# OuterMaskFinal.net
KiCad netlist of a schematic drawn in Altium Designer
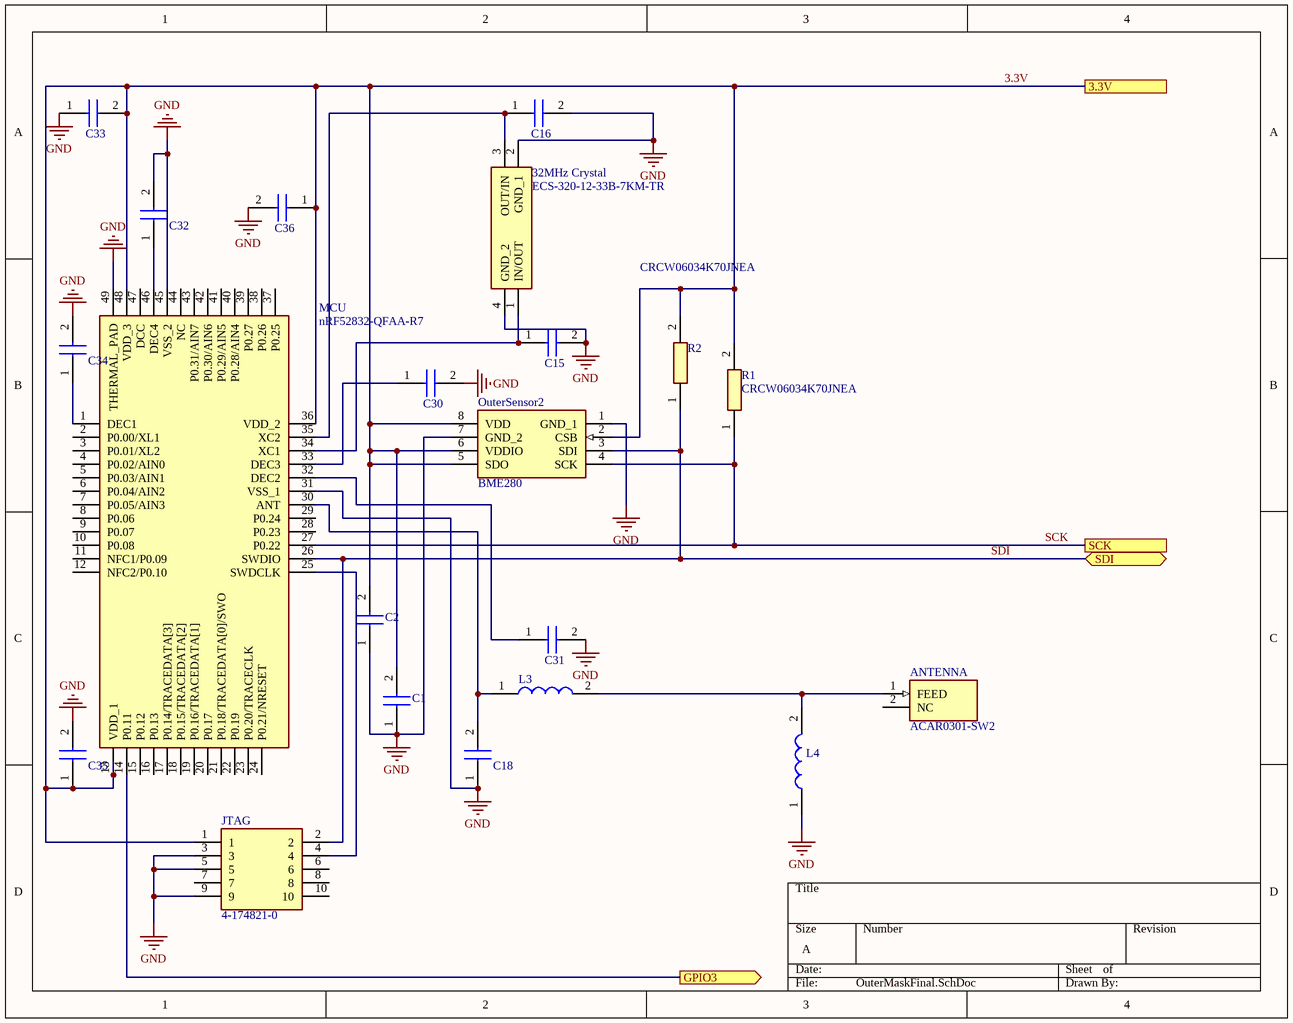
[diagram p0: OuterMaskFinal.SchDoc]

(export (version "E")
  (design (tool "Eeschema 10.0.6"))
  (components
    (comp (ref "32MHz Crystal")
      (value "ECS-320-12-33B-7KM-TR")
      (footprint "SamacSys:ECS3201233B7KMTR")
      (description "Crystal or Oscillator")
      (fields (field (name "MOUSER PART NUMBER") "520-320-12-33B-7KM-T"))
      (libsource (lib "*") (part "ECS-320-12-33B-7KM-TR"))
    )
    (comp (ref "ANTENNA")
      (value "ACAR0301-SW2")
      (footprint "SamacSys:ANTC3016X70N")
      (description "Antenna")
      (fields (field (name "MOUSER PART NUMBER") "815-ACAR0301-SW2"))
      (libsource (lib "*") (part "ACAR0301-SW2"))
    )
    (comp (ref "C1")
      (value "06033C334KAT2A")
      (footprint "SamacSys:CAPC1608X90N")
      (description "Capacitor")
      (fields (field (name "MOUSER PART NUMBER") "581-06033C334KAT2A"))
      (libsource (lib "*") (part "06033C334KAT2A"))
    )
    (comp (ref "C2")
      (value "06033C334KAT2A")
      (footprint "SamacSys:CAPC1608X90N")
      (description "Capacitor")
      (fields (field (name "MOUSER PART NUMBER") "581-06033C334KAT2A"))
      (libsource (lib "*") (part "06033C334KAT2A"))
    )
    (comp (ref "C15")
      (value "06033C334KAT2A")
      (footprint "SamacSys:CAPC1608X90N")
      (description "Capacitor")
      (fields (field (name "MOUSER PART NUMBER") "581-06033C334KAT2A"))
      (libsource (lib "*") (part "06033C334KAT2A"))
    )
    (comp (ref "C16")
      (value "06033C334KAT2A")
      (footprint "SamacSys:CAPC1608X90N")
      (description "Capacitor")
      (fields (field (name "MOUSER PART NUMBER") "581-06033C334KAT2A"))
      (libsource (lib "*") (part "06033C334KAT2A"))
    )
    (comp (ref "C18")
      (value "06033C334KAT2A")
      (footprint "SamacSys:CAPC1608X90N")
      (description "Capacitor")
      (fields (field (name "MOUSER PART NUMBER") "581-06033C334KAT2A"))
      (libsource (lib "*") (part "06033C334KAT2A"))
    )
    (comp (ref "C30")
      (value "06033C334KAT2A")
      (footprint "SamacSys:CAPC1608X90N")
      (description "Capacitor")
      (fields (field (name "MOUSER PART NUMBER") "581-06033C334KAT2A"))
      (libsource (lib "*") (part "06033C334KAT2A"))
    )
    (comp (ref "C31")
      (value "06033C334KAT2A")
      (footprint "SamacSys:CAPC1608X90N")
      (description "Capacitor")
      (fields (field (name "MOUSER PART NUMBER") "581-06033C334KAT2A"))
      (libsource (lib "*") (part "06033C334KAT2A"))
    )
    (comp (ref "C32")
      (value "06033C334KAT2A")
      (footprint "SamacSys:CAPC1608X90N")
      (description "Capacitor")
      (fields (field (name "MOUSER PART NUMBER") "581-06033C334KAT2A"))
      (libsource (lib "*") (part "06033C334KAT2A"))
    )
    (comp (ref "C33")
      (value "06033C334KAT2A")
      (footprint "SamacSys:CAPC1608X90N")
      (description "Capacitor")
      (fields (field (name "MOUSER PART NUMBER") "581-06033C334KAT2A"))
      (libsource (lib "*") (part "06033C334KAT2A"))
    )
    (comp (ref "C34")
      (value "06033C334KAT2A")
      (footprint "SamacSys:CAPC1608X90N")
      (description "Capacitor")
      (fields (field (name "MOUSER PART NUMBER") "581-06033C334KAT2A"))
      (libsource (lib "*") (part "06033C334KAT2A"))
    )
    (comp (ref "C35")
      (value "06033C334KAT2A")
      (footprint "SamacSys:CAPC1608X90N")
      (description "Capacitor")
      (fields (field (name "MOUSER PART NUMBER") "581-06033C334KAT2A"))
      (libsource (lib "*") (part "06033C334KAT2A"))
    )
    (comp (ref "C36")
      (value "06033C334KAT2A")
      (footprint "SamacSys:CAPC1608X90N")
      (description "Capacitor")
      (fields (field (name "MOUSER PART NUMBER") "581-06033C334KAT2A"))
      (libsource (lib "*") (part "06033C334KAT2A"))
    )
    (comp (ref "JTAG")
      (value "4-174821-0")
      (footprint "TE_4-174821-0")
      (description "Conn Fine Pitch Connector HDR 10 POS 1.25mm Solder ST SMD Loose Piece")
      (fields (field (name "MF") "TE Connectivity") (field (name "DIGI-KEY_PART_NUMBER") "A144930-ND"))
      (libsource (lib "4-174821-0") (part "4-174821-0"))
    )
    (comp (ref "L3")
      (value "0603CS-47NXGLU")
      (footprint "SamacSys:0603CS82NXGLW")
      (description "Inductor")
      (fields (field (name "MOUSER PART NUMBER") "994-0603CS-47NXGLU"))
      (libsource (lib "*") (part "0603CS-47NXGLU"))
    )
    (comp (ref "L4")
      (value "0603CS-47NXGLU")
      (footprint "SamacSys:0603CS82NXGLW")
      (description "Inductor")
      (fields (field (name "MOUSER PART NUMBER") "994-0603CS-47NXGLU"))
      (libsource (lib "*") (part "0603CS-47NXGLU"))
    )
    (comp (ref "MCU")
      (value "nRF52832-QFAA-R7")
      (footprint "SamacSys:QFN40P600X600X90-49N-D")
      (description "Integrated Circuit")
      (fields (field (name "MOUSER2 PART NUMBER") "949-NRF52832-QFAA-R7"))
      (libsource (lib "*") (part "nRF52832-QFAA-R7"))
    )
    (comp (ref "OuterSensor2")
      (value "BME280")
      (footprint "SamacSys:BME280")
      (description "Hygrometer")
      (fields (field (name "MOUSER PART NUMBER") "262-BME280"))
      (libsource (lib "*") (part "BME280"))
    )
    (comp (ref "R1")
      (value "CRCW06034K70JNEA")
      (footprint "SamacSys:RESC1608X50N")
      (description "Resistor")
      (fields (field (name "MOUSER PART NUMBER") "71-CRCW0603J-4.7K-E3"))
      (libsource (lib "*") (part "CRCW06034K70JNEA"))
    )
    (comp (ref "R2")
      (value "CRCW06034K70JNEA")
      (footprint "SamacSys:RESC1608X50N")
      (description "Resistor")
      (fields (field (name "MOUSER PART NUMBER") "71-CRCW0603J-4.7K-E3"))
      (libsource (lib "*") (part "CRCW06034K70JNEA"))
    )
  )
  (nets
    (net (code "1") (name "/3.3V") (class "Default")
      (node (ref "C1") (pin "2") (pinfunction "2_2") (pintype "passive"))
      (node (ref "C2") (pin "2") (pinfunction "2_2") (pintype "passive"))
      (node (ref "C33") (pin "2") (pinfunction "2_2") (pintype "passive"))
      (node (ref "C35") (pin "1") (pinfunction "1_1") (pintype "passive"))
      (node (ref "C36") (pin "1") (pinfunction "1_1") (pintype "passive"))
      (node (ref "JTAG") (pin "1") (pinfunction "1_1") (pintype "passive"))
      (node (ref "MCU") (pin "13") (pinfunction "VDD_1_13") (pintype "passive"))
      (node (ref "MCU") (pin "36") (pinfunction "VDD_2_36") (pintype "passive"))
      (node (ref "MCU") (pin "48") (pinfunction "VDD_3_48") (pintype "passive"))
      (node (ref "OuterSensor2") (pin "2") (pinfunction "CSB_2") (pintype "input"))
      (node (ref "OuterSensor2") (pin "5") (pinfunction "SDO_5") (pintype "passive"))
      (node (ref "OuterSensor2") (pin "6") (pinfunction "VDDIO_6") (pintype "power_in"))
      (node (ref "OuterSensor2") (pin "8") (pinfunction "VDD_8") (pintype "power_in"))
      (node (ref "R1") (pin "2") (pinfunction "2_2") (pintype "passive"))
      (node (ref "R2") (pin "2") (pinfunction "2_2") (pintype "passive"))
    )
    (net (code "2") (name "/GPIO3") (class "Default")
      (node (ref "MCU") (pin "14") (pinfunction "P0.11_14") (pintype "passive"))
    )
    (net (code "3") (name "/SCK") (class "Default")
      (node (ref "MCU") (pin "27") (pinfunction "P0.22_27") (pintype "passive"))
      (node (ref "OuterSensor2") (pin "4") (pinfunction "SCK_4") (pintype "passive"))
      (node (ref "R1") (pin "1") (pinfunction "1_1") (pintype "passive"))
    )
    (net (code "4") (name "/SDI") (class "Default")
      (node (ref "JTAG") (pin "2") (pinfunction "2_2") (pintype "passive"))
      (node (ref "MCU") (pin "26") (pinfunction "SWDIO_26") (pintype "passive"))
      (node (ref "OuterSensor2") (pin "3") (pinfunction "SDI_3") (pintype "passive"))
      (node (ref "R2") (pin "1") (pinfunction "1_1") (pintype "passive"))
    )
    (net (code "5") (name "GND") (class "Default")
      (node (ref "32MHz Crystal") (pin "2") (pinfunction "GND_1_2") (pintype "passive"))
      (node (ref "32MHz Crystal") (pin "4") (pinfunction "GND_2_4") (pintype "passive"))
      (node (ref "C1") (pin "1") (pinfunction "1_1") (pintype "passive"))
      (node (ref "C15") (pin "2") (pinfunction "2_2") (pintype "passive"))
      (node (ref "C16") (pin "2") (pinfunction "2_2") (pintype "passive"))
      (node (ref "C18") (pin "1") (pinfunction "1_1") (pintype "passive"))
      (node (ref "C2") (pin "1") (pinfunction "1_1") (pintype "passive"))
      (node (ref "C30") (pin "2") (pinfunction "2_2") (pintype "passive"))
      (node (ref "C31") (pin "2") (pinfunction "2_2") (pintype "passive"))
      (node (ref "C32") (pin "2") (pinfunction "2_2") (pintype "passive"))
      (node (ref "C33") (pin "1") (pinfunction "1_1") (pintype "passive"))
      (node (ref "C34") (pin "2") (pinfunction "2_2") (pintype "passive"))
      (node (ref "C35") (pin "2") (pinfunction "2_2") (pintype "passive"))
      (node (ref "C36") (pin "2") (pinfunction "2_2") (pintype "passive"))
      (node (ref "JTAG") (pin "3") (pinfunction "3_3") (pintype "passive"))
      (node (ref "JTAG") (pin "5") (pinfunction "5_5") (pintype "passive"))
      (node (ref "JTAG") (pin "9") (pinfunction "9_9") (pintype "passive"))
      (node (ref "L4") (pin "1") (pinfunction "1_1") (pintype "passive"))
      (node (ref "MCU") (pin "31") (pinfunction "VSS_1_31") (pintype "passive"))
      (node (ref "MCU") (pin "45") (pinfunction "VSS_2_45") (pintype "passive"))
      (node (ref "MCU") (pin "49") (pinfunction "THERMAL_PAD_49") (pintype "passive"))
      (node (ref "OuterSensor2") (pin "1") (pinfunction "GND_1_1") (pintype "power_in"))
      (node (ref "OuterSensor2") (pin "7") (pinfunction "GND_2_7") (pintype "power_in"))
    )
    (net (code "6") (name "Net-(32MHz Crystal-IN{slash}OUT)") (class "Default")
      (node (ref "32MHz Crystal") (pin "1") (pinfunction "IN/OUT_1") (pintype "passive"))
      (node (ref "C15") (pin "1") (pinfunction "1_1") (pintype "passive"))
      (node (ref "MCU") (pin "34") (pinfunction "XC1_34") (pintype "passive"))
    )
    (net (code "7") (name "Net-(32MHz Crystal-OUT{slash}IN)") (class "Default")
      (node (ref "32MHz Crystal") (pin "3") (pinfunction "OUT/IN_3") (pintype "passive"))
      (node (ref "C16") (pin "1") (pinfunction "1_1") (pintype "passive"))
      (node (ref "MCU") (pin "35") (pinfunction "XC2_35") (pintype "passive"))
    )
    (net (code "8") (name "Net-(ANTENNA-FEED)") (class "Default")
      (node (ref "ANTENNA") (pin "1") (pinfunction "FEED_1") (pintype "input"))
      (node (ref "L3") (pin "2") (pinfunction "2_2") (pintype "passive"))
      (node (ref "L4") (pin "2") (pinfunction "2_2") (pintype "passive"))
    )
    (net (code "9") (name "Net-(MCU-ANT)") (class "Default")
      (node (ref "C18") (pin "2") (pinfunction "2_2") (pintype "passive"))
      (node (ref "L3") (pin "1") (pinfunction "1_1") (pintype "passive"))
      (node (ref "MCU") (pin "30") (pinfunction "ANT_30") (pintype "passive"))
    )
    (net (code "10") (name "Net-(MCU-DEC1)") (class "Default")
      (node (ref "C34") (pin "1") (pinfunction "1_1") (pintype "passive"))
      (node (ref "MCU") (pin "1") (pinfunction "DEC1_1") (pintype "passive"))
    )
    (net (code "11") (name "Net-(MCU-DEC2)") (class "Default")
      (node (ref "C31") (pin "1") (pinfunction "1_1") (pintype "passive"))
      (node (ref "MCU") (pin "32") (pinfunction "DEC2_32") (pintype "passive"))
    )
    (net (code "12") (name "Net-(MCU-DEC3)") (class "Default")
      (node (ref "C30") (pin "1") (pinfunction "1_1") (pintype "passive"))
      (node (ref "MCU") (pin "33") (pinfunction "DEC3_33") (pintype "passive"))
    )
    (net (code "13") (name "Net-(MCU-DEC4)") (class "Default")
      (node (ref "C32") (pin "1") (pinfunction "1_1") (pintype "passive"))
      (node (ref "MCU") (pin "46") (pinfunction "DEC4_46") (pintype "passive"))
    )
    (net (code "14") (name "Net-(MCU-SWDCLK)") (class "Default")
      (node (ref "JTAG") (pin "4") (pinfunction "4_4") (pintype "passive"))
      (node (ref "MCU") (pin "25") (pinfunction "SWDCLK_25") (pintype "passive"))
    )
    (net (code "15") (name "unconnected-(ANTENNA-NC-Pad2)") (class "Default")
      (node (ref "ANTENNA") (pin "2") (pinfunction "NC_2") (pintype "passive"))
    )
    (net (code "16") (name "unconnected-(JTAG-Pad6)") (class "Default")
      (node (ref "JTAG") (pin "6") (pinfunction "6_6") (pintype "passive"))
    )
    (net (code "17") (name "unconnected-(JTAG-Pad7)") (class "Default")
      (node (ref "JTAG") (pin "7") (pinfunction "7_7") (pintype "passive"))
    )
    (net (code "18") (name "unconnected-(JTAG-Pad8)") (class "Default")
      (node (ref "JTAG") (pin "8") (pinfunction "8_8") (pintype "passive"))
    )
    (net (code "19") (name "unconnected-(JTAG-Pad10)") (class "Default")
      (node (ref "JTAG") (pin "10") (pinfunction "10_10") (pintype "passive"))
    )
    (net (code "20") (name "unconnected-(MCU-DCC-Pad47)") (class "Default")
      (node (ref "MCU") (pin "47") (pinfunction "DCC_47") (pintype "passive"))
    )
    (net (code "21") (name "unconnected-(MCU-NC-Pad44)") (class "Default")
      (node (ref "MCU") (pin "44") (pinfunction "NC_44") (pintype "passive"))
    )
    (net (code "22") (name "unconnected-(MCU-NFC1{slash}P0.09-Pad11)") (class "Default")
      (node (ref "MCU") (pin "11") (pinfunction "NFC1/P0.09_11") (pintype "passive"))
    )
    (net (code "23") (name "unconnected-(MCU-NFC2{slash}P0.10-Pad12)") (class "Default")
      (node (ref "MCU") (pin "12") (pinfunction "NFC2/P0.10_12") (pintype "passive"))
    )
    (net (code "24") (name "unconnected-(MCU-P0.00{slash}XL1-Pad2)") (class "Default")
      (node (ref "MCU") (pin "2") (pinfunction "P0.00/XL1_2") (pintype "passive"))
    )
    (net (code "25") (name "unconnected-(MCU-P0.01{slash}XL2-Pad3)") (class "Default")
      (node (ref "MCU") (pin "3") (pinfunction "P0.01/XL2_3") (pintype "passive"))
    )
    (net (code "26") (name "unconnected-(MCU-P0.02{slash}AIN0-Pad4)") (class "Default")
      (node (ref "MCU") (pin "4") (pinfunction "P0.02/AIN0_4") (pintype "passive"))
    )
    (net (code "27") (name "unconnected-(MCU-P0.03{slash}AIN1-Pad5)") (class "Default")
      (node (ref "MCU") (pin "5") (pinfunction "P0.03/AIN1_5") (pintype "passive"))
    )
    (net (code "28") (name "unconnected-(MCU-P0.04{slash}AIN2-Pad6)") (class "Default")
      (node (ref "MCU") (pin "6") (pinfunction "P0.04/AIN2_6") (pintype "passive"))
    )
    (net (code "29") (name "unconnected-(MCU-P0.05{slash}AIN3-Pad7)") (class "Default")
      (node (ref "MCU") (pin "7") (pinfunction "P0.05/AIN3_7") (pintype "passive"))
    )
    (net (code "30") (name "unconnected-(MCU-P0.06-Pad8)") (class "Default")
      (node (ref "MCU") (pin "8") (pinfunction "P0.06_8") (pintype "passive"))
    )
    (net (code "31") (name "unconnected-(MCU-P0.07-Pad9)") (class "Default")
      (node (ref "MCU") (pin "9") (pinfunction "P0.07_9") (pintype "passive"))
    )
    (net (code "32") (name "unconnected-(MCU-P0.08-Pad10)") (class "Default")
      (node (ref "MCU") (pin "10") (pinfunction "P0.08_10") (pintype "passive"))
    )
    (net (code "33") (name "unconnected-(MCU-P0.12-Pad15)") (class "Default")
      (node (ref "MCU") (pin "15") (pinfunction "P0.12_15") (pintype "passive"))
    )
    (net (code "34") (name "unconnected-(MCU-P0.13-Pad16)") (class "Default")
      (node (ref "MCU") (pin "16") (pinfunction "P0.13_16") (pintype "passive"))
    )
    (net (code "35") (name "unconnected-(MCU-P0.14{slash}TRACEDATA[3]-Pad17)") (class "Default")
      (node (ref "MCU") (pin "17") (pinfunction "P0.14/TRACEDATA[3]_17") (pintype "passive"))
    )
    (net (code "36") (name "unconnected-(MCU-P0.15{slash}TRACEDATA[2]-Pad18)") (class "Default")
      (node (ref "MCU") (pin "18") (pinfunction "P0.15/TRACEDATA[2]_18") (pintype "passive"))
    )
    (net (code "37") (name "unconnected-(MCU-P0.16{slash}TRACEDATA[1]-Pad19)") (class "Default")
      (node (ref "MCU") (pin "19") (pinfunction "P0.16/TRACEDATA[1]_19") (pintype "passive"))
    )
    (net (code "38") (name "unconnected-(MCU-P0.17-Pad20)") (class "Default")
      (node (ref "MCU") (pin "20") (pinfunction "P0.17_20") (pintype "passive"))
    )
    (net (code "39") (name "unconnected-(MCU-P0.18{slash}TRACEDATA[0]{slash}SWO-Pad21)") (class "Default")
      (node (ref "MCU") (pin "21") (pinfunction "P0.18/TRACEDATA[0]/SWO_21") (pintype "passive"))
    )
    (net (code "40") (name "unconnected-(MCU-P0.19-Pad22)") (class "Default")
      (node (ref "MCU") (pin "22") (pinfunction "P0.19_22") (pintype "passive"))
    )
    (net (code "41") (name "unconnected-(MCU-P0.20{slash}TRACECLK-Pad23)") (class "Default")
      (node (ref "MCU") (pin "23") (pinfunction "P0.20/TRACECLK_23") (pintype "passive"))
    )
    (net (code "42") (name "unconnected-(MCU-P0.21{slash}NRESET-Pad24)") (class "Default")
      (node (ref "MCU") (pin "24") (pinfunction "P0.21/NRESET_24") (pintype "passive"))
    )
    (net (code "43") (name "unconnected-(MCU-P0.23-Pad28)") (class "Default")
      (node (ref "MCU") (pin "28") (pinfunction "P0.23_28") (pintype "passive"))
    )
    (net (code "44") (name "unconnected-(MCU-P0.24-Pad29)") (class "Default")
      (node (ref "MCU") (pin "29") (pinfunction "P0.24_29") (pintype "passive"))
    )
    (net (code "45") (name "unconnected-(MCU-P0.25-Pad37)") (class "Default")
      (node (ref "MCU") (pin "37") (pinfunction "P0.25_37") (pintype "passive"))
    )
    (net (code "46") (name "unconnected-(MCU-P0.26-Pad38)") (class "Default")
      (node (ref "MCU") (pin "38") (pinfunction "P0.26_38") (pintype "passive"))
    )
    (net (code "47") (name "unconnected-(MCU-P0.27-Pad39)") (class "Default")
      (node (ref "MCU") (pin "39") (pinfunction "P0.27_39") (pintype "passive"))
    )
    (net (code "48") (name "unconnected-(MCU-P0.28{slash}AIN4-Pad40)") (class "Default")
      (node (ref "MCU") (pin "40") (pinfunction "P0.28/AIN4_40") (pintype "passive"))
    )
    (net (code "49") (name "unconnected-(MCU-P0.29{slash}AIN5-Pad41)") (class "Default")
      (node (ref "MCU") (pin "41") (pinfunction "P0.29/AIN5_41") (pintype "passive"))
    )
    (net (code "50") (name "unconnected-(MCU-P0.30{slash}AIN6-Pad42)") (class "Default")
      (node (ref "MCU") (pin "42") (pinfunction "P0.30/AIN6_42") (pintype "passive"))
    )
    (net (code "51") (name "unconnected-(MCU-P0.31{slash}AIN7-Pad43)") (class "Default")
      (node (ref "MCU") (pin "43") (pinfunction "P0.31/AIN7_43") (pintype "passive"))
    )
  )
)
